# nixienet.net
KiCad netlist of a schematic drawn in EAGLE
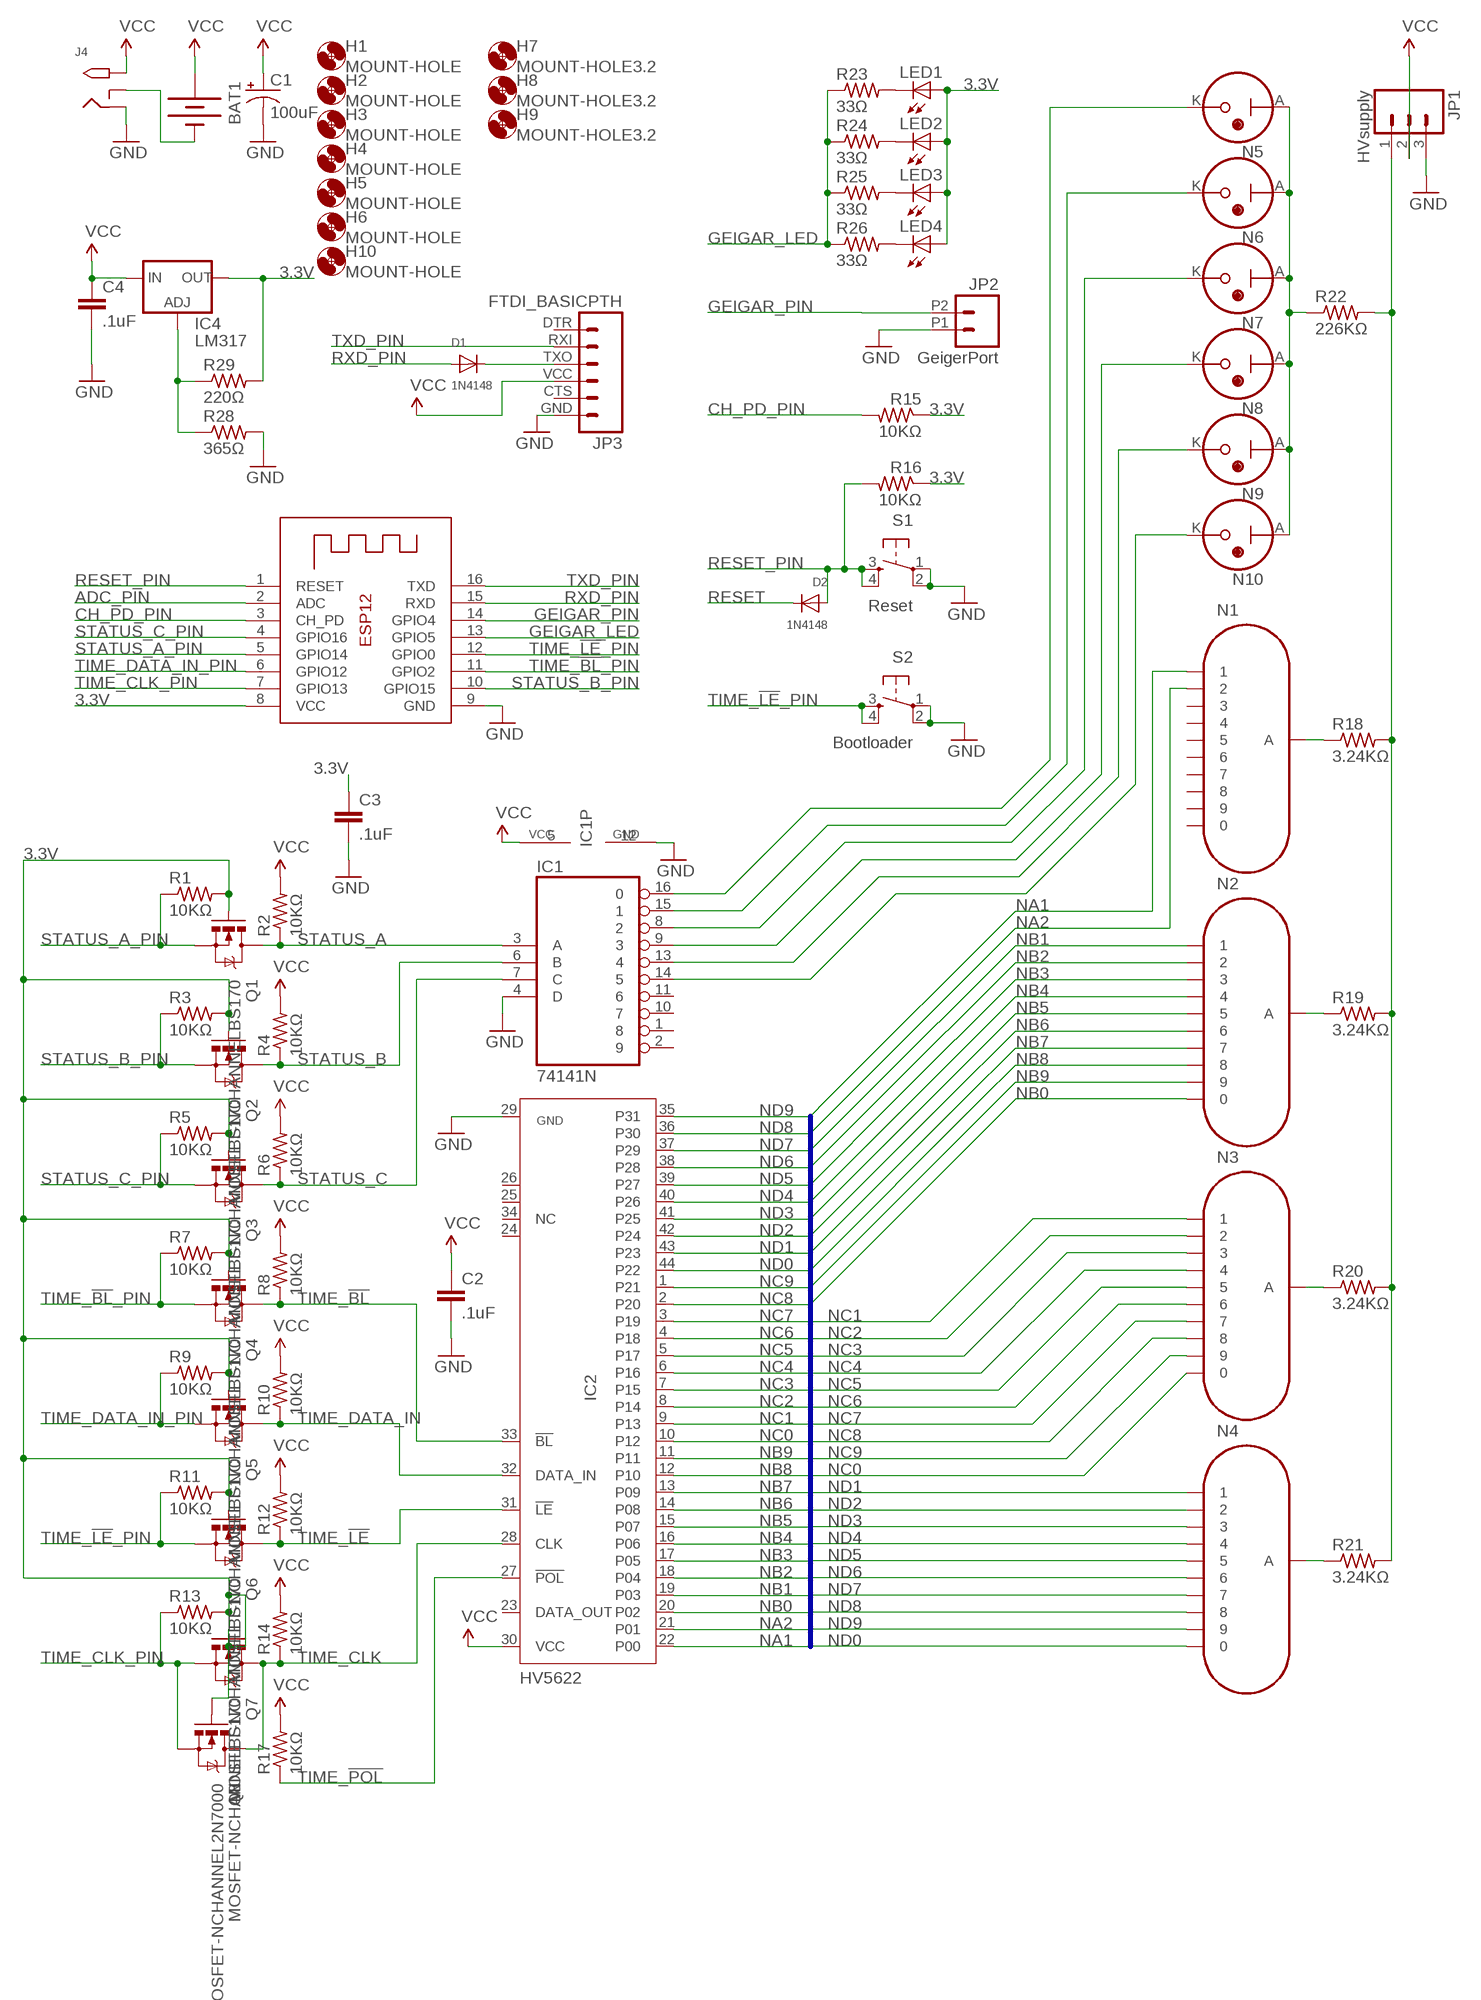
[diagram p0: schematic, sheet 1]

(export (version "E")
  (design (tool "Eeschema 10.0.6"))
  (components
    (comp (ref "BAT1")
      (value "BATTERY9V")
      (footprint "eagle-import:BATTCON_9V")
      (libsource (lib "eagle-import") (part "BATTERY9V"))
    )
    (comp (ref "C1")
      (value "100uF")
      (footprint "eagle-import:E5-8,5")
      (libsource (lib "eagle-import") (part "CPOL-USE5-8.5"))
    )
    (comp (ref "C2")
      (value ".1uF")
      (footprint "eagle-import:CAP-PTH-SMALLEZ")
      (libsource (lib "eagle-import") (part "CAPEZ"))
    )
    (comp (ref "C3")
      (value ".1uF")
      (footprint "eagle-import:CAP-PTH-SMALLEZ")
      (libsource (lib "eagle-import") (part "CAPEZ"))
    )
    (comp (ref "C4")
      (value ".1uF")
      (footprint "eagle-import:CAP-PTH-SMALLEZ")
      (libsource (lib "eagle-import") (part "CAPEZ"))
    )
    (comp (ref "D1")
      (value "1N4148")
      (footprint "eagle-import:1N4148")
      (libsource (lib "eagle-import") (part "DIODE"))
    )
    (comp (ref "D2")
      (value "1N4148")
      (footprint "eagle-import:1N4148")
      (libsource (lib "eagle-import") (part "DIODE"))
    )
    (comp (ref "H1")
      (value "MOUNT-HOLE")
      (footprint "eagle-import:3,2-DANGER")
      (libsource (lib "eagle-import") (part "MOUNT-HOLE"))
    )
    (comp (ref "H2")
      (value "MOUNT-HOLE")
      (footprint "eagle-import:3,2-DANGER")
      (libsource (lib "eagle-import") (part "MOUNT-HOLE"))
    )
    (comp (ref "H3")
      (value "MOUNT-HOLE")
      (footprint "eagle-import:3,2-DANGER")
      (libsource (lib "eagle-import") (part "MOUNT-HOLE"))
    )
    (comp (ref "H4")
      (value "MOUNT-HOLE")
      (footprint "eagle-import:3,2-DANGER")
      (libsource (lib "eagle-import") (part "MOUNT-HOLE"))
    )
    (comp (ref "H5")
      (value "MOUNT-HOLE")
      (footprint "eagle-import:3,2-DANGER")
      (libsource (lib "eagle-import") (part "MOUNT-HOLE"))
    )
    (comp (ref "H6")
      (value "MOUNT-HOLE")
      (footprint "eagle-import:3,2-DANGER")
      (libsource (lib "eagle-import") (part "MOUNT-HOLE"))
    )
    (comp (ref "H7")
      (value "MOUNT-HOLE3.2")
      (footprint "eagle-import:3,2")
      (libsource (lib "eagle-import") (part "MOUNT-HOLE3.2"))
    )
    (comp (ref "H8")
      (value "MOUNT-HOLE3.2")
      (footprint "eagle-import:3,2")
      (libsource (lib "eagle-import") (part "MOUNT-HOLE3.2"))
    )
    (comp (ref "H9")
      (value "MOUNT-HOLE3.2")
      (footprint "eagle-import:3,2")
      (libsource (lib "eagle-import") (part "MOUNT-HOLE3.2"))
    )
    (comp (ref "H10")
      (value "MOUNT-HOLE")
      (footprint "eagle-import:3,2-DANGER")
      (libsource (lib "eagle-import") (part "MOUNT-HOLE"))
    )
    (comp (ref "IC1")
      (value "74141N")
      (footprint "eagle-import:DIL16")
      (libsource (lib "eagle-import") (part "74141N"))
    )
    (comp (ref "IC2")
      (value "HV5622")
      (footprint "eagle-import:QFP44")
      (libsource (lib "eagle-import") (part "HV5622"))
    )
    (comp (ref "IC3")
      (value "ESP-12")
      (footprint "eagle-import:ESP-12")
      (libsource (lib "eagle-import") (part "ESP-12"))
    )
    (comp (ref "IC4")
      (value "LM317")
      (footprint "eagle-import:SPARKFUN-POWERIC_TO220-ADJ")
      (libsource (lib "eagle-import") (part "SPARKFUN-POWERIC_V_REG_317SINK"))
    )
    (comp (ref "J4")
      (value "2.1MMJACKTHM")
      (footprint "eagle-import:PJ-102A")
      (libsource (lib "eagle-import") (part "2.1MMJACKTHM"))
    )
    (comp (ref "JP1")
      (value "HVsupply")
      (footprint "eagle-import:SCREWTERMINAL-5MM-3")
      (libsource (lib "eagle-import") (part "M03-SCREW-5MM"))
    )
    (comp (ref "JP2")
      (value "GeigerPort")
      (footprint "eagle-import:1X02_2.54_SCREWTERM")
      (libsource (lib "eagle-import") (part "M022.54MM_SCREWTERM"))
    )
    (comp (ref "JP3")
      (value "FTDI_BASICPTH")
      (footprint "eagle-import:FTDI_BASIC")
      (libsource (lib "eagle-import") (part "FTDI_BASICPTH"))
    )
    (comp (ref "LED1")
      (value "LED5MM")
      (footprint "eagle-import:LED5MM")
      (libsource (lib "eagle-import") (part "LED5MM"))
    )
    (comp (ref "LED2")
      (value "LED5MM")
      (footprint "eagle-import:LED5MM")
      (libsource (lib "eagle-import") (part "LED5MM"))
    )
    (comp (ref "LED3")
      (value "LED5MM")
      (footprint "eagle-import:LED5MM")
      (libsource (lib "eagle-import") (part "LED5MM"))
    )
    (comp (ref "LED4")
      (value "LED5MM")
      (footprint "eagle-import:LED5MM")
      (libsource (lib "eagle-import") (part "LED5MM"))
    )
    (comp (ref "N1")
      (value "Hour1")
      (footprint "eagle-import:IN-18")
      (libsource (lib "eagle-import") (part "IN-4"))
    )
    (comp (ref "N2")
      (value "Hour2")
      (footprint "eagle-import:IN-18")
      (libsource (lib "eagle-import") (part "IN-4"))
    )
    (comp (ref "N3")
      (value "Minutes1")
      (footprint "eagle-import:IN-18")
      (libsource (lib "eagle-import") (part "IN-4"))
    )
    (comp (ref "N4")
      (value "Minutes2")
      (footprint "eagle-import:IN-18")
      (libsource (lib "eagle-import") (part "IN-4"))
    )
    (comp (ref "N5")
      (value "TopBulb")
      (footprint "eagle-import:INS-1")
      (libsource (lib "eagle-import") (part "INS-1"))
    )
    (comp (ref "N6")
      (value "BottomBulb")
      (footprint "eagle-import:INS-1")
      (libsource (lib "eagle-import") (part "INS-1"))
    )
    (comp (ref "N7")
      (value "SunnyBulb")
      (footprint "eagle-import:INS-1")
      (libsource (lib "eagle-import") (part "INS-1"))
    )
    (comp (ref "N8")
      (value "CloudyBulb")
      (footprint "eagle-import:INS-1")
      (libsource (lib "eagle-import") (part "INS-1"))
    )
    (comp (ref "N9")
      (value "RainyBulb")
      (footprint "eagle-import:INS-1")
      (libsource (lib "eagle-import") (part "INS-1"))
    )
    (comp (ref "N10")
      (value "SnowyBulb")
      (footprint "eagle-import:INS-1")
      (libsource (lib "eagle-import") (part "INS-1"))
    )
    (comp (ref "Q1")
      (value "MOSFET-NCHANNELBS170")
      (footprint "eagle-import:TO-92")
      (libsource (lib "eagle-import") (part "MOSFET-NCHANNELBS170"))
    )
    (comp (ref "Q2")
      (value "MOSFET-NCHANNELBS170")
      (footprint "eagle-import:TO-92")
      (libsource (lib "eagle-import") (part "MOSFET-NCHANNELBS170"))
    )
    (comp (ref "Q3")
      (value "MOSFET-NCHANNELBS170")
      (footprint "eagle-import:TO-92")
      (libsource (lib "eagle-import") (part "MOSFET-NCHANNELBS170"))
    )
    (comp (ref "Q4")
      (value "MOSFET-NCHANNELBS170")
      (footprint "eagle-import:TO-92")
      (libsource (lib "eagle-import") (part "MOSFET-NCHANNELBS170"))
    )
    (comp (ref "Q5")
      (value "MOSFET-NCHANNELBS170")
      (footprint "eagle-import:TO-92")
      (libsource (lib "eagle-import") (part "MOSFET-NCHANNELBS170"))
    )
    (comp (ref "Q6")
      (value "MOSFET-NCHANNELBS170")
      (footprint "eagle-import:TO-92")
      (libsource (lib "eagle-import") (part "MOSFET-NCHANNELBS170"))
    )
    (comp (ref "Q7")
      (value "MOSFET-NCHANNELBS170")
      (footprint "eagle-import:TO-92")
      (libsource (lib "eagle-import") (part "MOSFET-NCHANNELBS170"))
    )
    (comp (ref "Q8")
      (value "MOSFET-NCHANNEL2N7000")
      (footprint "eagle-import:TO-92")
      (libsource (lib "eagle-import") (part "MOSFET-NCHANNEL2N7000"))
    )
    (comp (ref "R1")
      (value "10KΩ")
      (footprint "eagle-import:0204_5")
      (libsource (lib "eagle-import") (part "R-US_0204/5"))
    )
    (comp (ref "R2")
      (value "10KΩ")
      (footprint "eagle-import:0204_5")
      (libsource (lib "eagle-import") (part "R-US_0204/5"))
    )
    (comp (ref "R3")
      (value "10KΩ")
      (footprint "eagle-import:0204_5")
      (libsource (lib "eagle-import") (part "R-US_0204/5"))
    )
    (comp (ref "R4")
      (value "10KΩ")
      (footprint "eagle-import:0204_5")
      (libsource (lib "eagle-import") (part "R-US_0204/5"))
    )
    (comp (ref "R5")
      (value "10KΩ")
      (footprint "eagle-import:0204_5")
      (libsource (lib "eagle-import") (part "R-US_0204/5"))
    )
    (comp (ref "R6")
      (value "10KΩ")
      (footprint "eagle-import:0204_5")
      (libsource (lib "eagle-import") (part "R-US_0204/5"))
    )
    (comp (ref "R7")
      (value "10KΩ")
      (footprint "eagle-import:0204_5")
      (libsource (lib "eagle-import") (part "R-US_0204/5"))
    )
    (comp (ref "R8")
      (value "10KΩ")
      (footprint "eagle-import:0204_5")
      (libsource (lib "eagle-import") (part "R-US_0204/5"))
    )
    (comp (ref "R9")
      (value "10KΩ")
      (footprint "eagle-import:0204_5")
      (libsource (lib "eagle-import") (part "R-US_0204/5"))
    )
    (comp (ref "R10")
      (value "10KΩ")
      (footprint "eagle-import:0204_5")
      (libsource (lib "eagle-import") (part "R-US_0204/5"))
    )
    (comp (ref "R11")
      (value "10KΩ")
      (footprint "eagle-import:0204_5")
      (libsource (lib "eagle-import") (part "R-US_0204/5"))
    )
    (comp (ref "R12")
      (value "10KΩ")
      (footprint "eagle-import:0204_5")
      (libsource (lib "eagle-import") (part "R-US_0204/5"))
    )
    (comp (ref "R13")
      (value "10KΩ")
      (footprint "eagle-import:0204_5")
      (libsource (lib "eagle-import") (part "R-US_0204/5"))
    )
    (comp (ref "R14")
      (value "10KΩ")
      (footprint "eagle-import:0204_5")
      (libsource (lib "eagle-import") (part "R-US_0204/5"))
    )
    (comp (ref "R15")
      (value "10KΩ")
      (footprint "eagle-import:0204_5")
      (libsource (lib "eagle-import") (part "R-US_0204/5"))
    )
    (comp (ref "R16")
      (value "10KΩ")
      (footprint "eagle-import:0204_5")
      (libsource (lib "eagle-import") (part "R-US_0204/5"))
    )
    (comp (ref "R17")
      (value "10KΩ")
      (footprint "eagle-import:0204_5")
      (libsource (lib "eagle-import") (part "R-US_0204/5"))
    )
    (comp (ref "R18")
      (value "3.24KΩ")
      (footprint "eagle-import:0204_5")
      (libsource (lib "eagle-import") (part "R-US_0204/5"))
    )
    (comp (ref "R19")
      (value "3.24KΩ")
      (footprint "eagle-import:0204_5")
      (libsource (lib "eagle-import") (part "R-US_0204/5"))
    )
    (comp (ref "R20")
      (value "3.24KΩ")
      (footprint "eagle-import:0204_5")
      (libsource (lib "eagle-import") (part "R-US_0204/5"))
    )
    (comp (ref "R21")
      (value "3.24KΩ")
      (footprint "eagle-import:0204_5")
      (libsource (lib "eagle-import") (part "R-US_0204/5"))
    )
    (comp (ref "R22")
      (value "226KΩ")
      (footprint "eagle-import:0204_5")
      (libsource (lib "eagle-import") (part "R-US_0204/5"))
    )
    (comp (ref "R23")
      (value "33Ω")
      (footprint "eagle-import:0204_5")
      (libsource (lib "eagle-import") (part "R-US_0204/5"))
    )
    (comp (ref "R24")
      (value "33Ω")
      (footprint "eagle-import:0204_5")
      (libsource (lib "eagle-import") (part "R-US_0204/5"))
    )
    (comp (ref "R25")
      (value "33Ω")
      (footprint "eagle-import:0204_5")
      (libsource (lib "eagle-import") (part "R-US_0204/5"))
    )
    (comp (ref "R26")
      (value "33Ω")
      (footprint "eagle-import:0204_5")
      (libsource (lib "eagle-import") (part "R-US_0204/5"))
    )
    (comp (ref "R28")
      (value "365Ω")
      (footprint "eagle-import:0204_5")
      (libsource (lib "eagle-import") (part "R-US_0204/5"))
    )
    (comp (ref "R29")
      (value "220Ω")
      (footprint "eagle-import:0204_5")
      (libsource (lib "eagle-import") (part "R-US_0204/5"))
    )
    (comp (ref "S1")
      (value "Reset")
      (footprint "eagle-import:TACTILE-PTH")
      (libsource (lib "eagle-import") (part "TAC_SWITCHPTH"))
    )
    (comp (ref "S2")
      (value "Bootloader")
      (footprint "eagle-import:TACTILE-PTH")
      (libsource (lib "eagle-import") (part "TAC_SWITCHPTH"))
    )
  )
  (nets
    (net (code "1") (name "/3.3V") (class "Default")
      (node (ref "C3") (pin "1") (pinfunction "1_1") (pintype "passive"))
      (node (ref "IC3") (pin "8") (pinfunction "VCC_8") (pintype "power_in"))
      (node (ref "IC4") (pin "OUT") (pinfunction "OUT_OUT") (pintype "output"))
      (node (ref "LED1") (pin "A") (pinfunction "A_A") (pintype "passive"))
      (node (ref "LED2") (pin "A") (pinfunction "A_A") (pintype "passive"))
      (node (ref "LED3") (pin "A") (pinfunction "A_A") (pintype "passive"))
      (node (ref "LED4") (pin "A") (pinfunction "A_A") (pintype "passive"))
      (node (ref "Q1") (pin "2") (pinfunction "G_2") (pintype "passive"))
      (node (ref "Q2") (pin "2") (pinfunction "G_2") (pintype "passive"))
      (node (ref "Q3") (pin "2") (pinfunction "G_2") (pintype "passive"))
      (node (ref "Q4") (pin "2") (pinfunction "G_2") (pintype "passive"))
      (node (ref "Q5") (pin "2") (pinfunction "G_2") (pintype "passive"))
      (node (ref "Q6") (pin "2") (pinfunction "G_2") (pintype "passive"))
      (node (ref "Q7") (pin "2") (pinfunction "G_2") (pintype "passive"))
      (node (ref "Q8") (pin "2") (pinfunction "G_2") (pintype "passive"))
      (node (ref "R1") (pin "2") (pinfunction "2_2") (pintype "passive"))
      (node (ref "R11") (pin "2") (pinfunction "2_2") (pintype "passive"))
      (node (ref "R13") (pin "2") (pinfunction "2_2") (pintype "passive"))
      (node (ref "R15") (pin "1") (pinfunction "1_1") (pintype "passive"))
      (node (ref "R16") (pin "1") (pinfunction "1_1") (pintype "passive"))
      (node (ref "R29") (pin "2") (pinfunction "2_2") (pintype "passive"))
      (node (ref "R3") (pin "2") (pinfunction "2_2") (pintype "passive"))
      (node (ref "R5") (pin "2") (pinfunction "2_2") (pintype "passive"))
      (node (ref "R7") (pin "2") (pinfunction "2_2") (pintype "passive"))
      (node (ref "R9") (pin "2") (pinfunction "2_2") (pintype "passive"))
    )
    (net (code "2") (name "/ADC_PIN") (class "Default")
      (node (ref "IC3") (pin "2") (pinfunction "ADC_2") (pintype "passive"))
    )
    (net (code "3") (name "/CH_PD_PIN") (class "Default")
      (node (ref "IC3") (pin "3") (pinfunction "CH_PD_3") (pintype "input"))
      (node (ref "R15") (pin "2") (pinfunction "2_2") (pintype "passive"))
    )
    (net (code "4") (name "/GEIGAR_LED") (class "Default")
      (node (ref "IC3") (pin "13") (pinfunction "GPIO5_13") (pintype "bidirectional"))
      (node (ref "R23") (pin "1") (pinfunction "1_1") (pintype "passive"))
      (node (ref "R24") (pin "1") (pinfunction "1_1") (pintype "passive"))
      (node (ref "R25") (pin "1") (pinfunction "1_1") (pintype "passive"))
      (node (ref "R26") (pin "1") (pinfunction "1_1") (pintype "passive"))
    )
    (net (code "5") (name "/GEIGAR_PIN") (class "Default")
      (node (ref "IC3") (pin "14") (pinfunction "GPIO4_14") (pintype "bidirectional"))
      (node (ref "JP2") (pin "P2") (pinfunction "2_P2") (pintype "passive"))
    )
    (net (code "6") (name "/NA1") (class "Default")
      (node (ref "IC2") (pin "22") (pinfunction "P00_22") (pintype "bidirectional"))
      (node (ref "N1") (pin "14") (pinfunction "1_14") (pintype "bidirectional"))
    )
    (net (code "7") (name "/NA2") (class "Default")
      (node (ref "IC2") (pin "21") (pinfunction "P01_21") (pintype "bidirectional"))
      (node (ref "N1") (pin "9") (pinfunction "2_9") (pintype "bidirectional"))
    )
    (net (code "8") (name "/NB0") (class "Default")
      (node (ref "IC2") (pin "20") (pinfunction "P02_20") (pintype "bidirectional"))
      (node (ref "N2") (pin "8") (pinfunction "0_8") (pintype "bidirectional"))
    )
    (net (code "9") (name "/NB1") (class "Default")
      (node (ref "IC2") (pin "19") (pinfunction "P03_19") (pintype "bidirectional"))
      (node (ref "N2") (pin "14") (pinfunction "1_14") (pintype "bidirectional"))
    )
    (net (code "10") (name "/NB2") (class "Default")
      (node (ref "IC2") (pin "18") (pinfunction "P04_18") (pintype "bidirectional"))
      (node (ref "N2") (pin "9") (pinfunction "2_9") (pintype "bidirectional"))
    )
    (net (code "11") (name "/NB3") (class "Default")
      (node (ref "IC2") (pin "17") (pinfunction "P05_17") (pintype "bidirectional"))
      (node (ref "N2") (pin "11") (pinfunction "3_11") (pintype "bidirectional"))
    )
    (net (code "12") (name "/NB4") (class "Default")
      (node (ref "IC2") (pin "16") (pinfunction "P06_16") (pintype "bidirectional"))
      (node (ref "N2") (pin "1") (pinfunction "4_1") (pintype "bidirectional"))
    )
    (net (code "13") (name "/NB5") (class "Default")
      (node (ref "IC2") (pin "15") (pinfunction "P07_15") (pintype "bidirectional"))
      (node (ref "N2") (pin "12") (pinfunction "5_12") (pintype "bidirectional"))
    )
    (net (code "14") (name "/NB6") (class "Default")
      (node (ref "IC2") (pin "14") (pinfunction "P08_14") (pintype "bidirectional"))
      (node (ref "N2") (pin "2") (pinfunction "6_2") (pintype "bidirectional"))
    )
    (net (code "15") (name "/NB7") (class "Default")
      (node (ref "IC2") (pin "13") (pinfunction "P09_13") (pintype "bidirectional"))
      (node (ref "N2") (pin "6") (pinfunction "7_6") (pintype "bidirectional"))
    )
    (net (code "16") (name "/NB8") (class "Default")
      (node (ref "IC2") (pin "12") (pinfunction "P10_12") (pintype "bidirectional"))
      (node (ref "N2") (pin "3") (pinfunction "8_3") (pintype "bidirectional"))
    )
    (net (code "17") (name "/NB9") (class "Default")
      (node (ref "IC2") (pin "11") (pinfunction "P11_11") (pintype "bidirectional"))
      (node (ref "N2") (pin "5") (pinfunction "9_5") (pintype "bidirectional"))
    )
    (net (code "18") (name "/NC0") (class "Default")
      (node (ref "IC2") (pin "10") (pinfunction "P12_10") (pintype "bidirectional"))
      (node (ref "N3") (pin "8") (pinfunction "0_8") (pintype "bidirectional"))
    )
    (net (code "19") (name "/NC1") (class "Default")
      (node (ref "IC2") (pin "9") (pinfunction "P13_9") (pintype "bidirectional"))
      (node (ref "N3") (pin "14") (pinfunction "1_14") (pintype "bidirectional"))
    )
    (net (code "20") (name "/NC2") (class "Default")
      (node (ref "IC2") (pin "8") (pinfunction "P14_8") (pintype "bidirectional"))
      (node (ref "N3") (pin "9") (pinfunction "2_9") (pintype "bidirectional"))
    )
    (net (code "21") (name "/NC3") (class "Default")
      (node (ref "IC2") (pin "7") (pinfunction "P15_7") (pintype "bidirectional"))
      (node (ref "N3") (pin "11") (pinfunction "3_11") (pintype "bidirectional"))
    )
    (net (code "22") (name "/NC4") (class "Default")
      (node (ref "IC2") (pin "6") (pinfunction "P16_6") (pintype "bidirectional"))
      (node (ref "N3") (pin "1") (pinfunction "4_1") (pintype "bidirectional"))
    )
    (net (code "23") (name "/NC5") (class "Default")
      (node (ref "IC2") (pin "5") (pinfunction "P17_5") (pintype "bidirectional"))
      (node (ref "N3") (pin "12") (pinfunction "5_12") (pintype "bidirectional"))
    )
    (net (code "24") (name "/NC6") (class "Default")
      (node (ref "IC2") (pin "4") (pinfunction "P18_4") (pintype "bidirectional"))
      (node (ref "N3") (pin "2") (pinfunction "6_2") (pintype "bidirectional"))
    )
    (net (code "25") (name "/NC7") (class "Default")
      (node (ref "IC2") (pin "3") (pinfunction "P19_3") (pintype "bidirectional"))
      (node (ref "N3") (pin "6") (pinfunction "7_6") (pintype "bidirectional"))
    )
    (net (code "26") (name "/NC8") (class "Default")
      (node (ref "IC2") (pin "2") (pinfunction "P20_2") (pintype "bidirectional"))
      (node (ref "N3") (pin "3") (pinfunction "8_3") (pintype "bidirectional"))
    )
    (net (code "27") (name "/NC9") (class "Default")
      (node (ref "IC2") (pin "1") (pinfunction "P21_1") (pintype "bidirectional"))
      (node (ref "N3") (pin "5") (pinfunction "9_5") (pintype "bidirectional"))
    )
    (net (code "28") (name "/ND0") (class "Default")
      (node (ref "IC2") (pin "44") (pinfunction "P22_44") (pintype "bidirectional"))
      (node (ref "N4") (pin "8") (pinfunction "0_8") (pintype "bidirectional"))
    )
    (net (code "29") (name "/ND1") (class "Default")
      (node (ref "IC2") (pin "43") (pinfunction "P23_43") (pintype "bidirectional"))
      (node (ref "N4") (pin "14") (pinfunction "1_14") (pintype "bidirectional"))
    )
    (net (code "30") (name "/ND2") (class "Default")
      (node (ref "IC2") (pin "42") (pinfunction "P24_42") (pintype "bidirectional"))
      (node (ref "N4") (pin "9") (pinfunction "2_9") (pintype "bidirectional"))
    )
    (net (code "31") (name "/ND3") (class "Default")
      (node (ref "IC2") (pin "41") (pinfunction "P25_41") (pintype "bidirectional"))
      (node (ref "N4") (pin "11") (pinfunction "3_11") (pintype "bidirectional"))
    )
    (net (code "32") (name "/ND4") (class "Default")
      (node (ref "IC2") (pin "40") (pinfunction "P26_40") (pintype "bidirectional"))
      (node (ref "N4") (pin "1") (pinfunction "4_1") (pintype "bidirectional"))
    )
    (net (code "33") (name "/ND5") (class "Default")
      (node (ref "IC2") (pin "39") (pinfunction "P27_39") (pintype "bidirectional"))
      (node (ref "N4") (pin "12") (pinfunction "5_12") (pintype "bidirectional"))
    )
    (net (code "34") (name "/ND6") (class "Default")
      (node (ref "IC2") (pin "38") (pinfunction "P28_38") (pintype "bidirectional"))
      (node (ref "N4") (pin "2") (pinfunction "6_2") (pintype "bidirectional"))
    )
    (net (code "35") (name "/ND7") (class "Default")
      (node (ref "IC2") (pin "37") (pinfunction "P29_37") (pintype "bidirectional"))
      (node (ref "N4") (pin "6") (pinfunction "7_6") (pintype "bidirectional"))
    )
    (net (code "36") (name "/ND8") (class "Default")
      (node (ref "IC2") (pin "36") (pinfunction "P30_36") (pintype "bidirectional"))
      (node (ref "N4") (pin "3") (pinfunction "8_3") (pintype "bidirectional"))
    )
    (net (code "37") (name "/ND9") (class "Default")
      (node (ref "IC2") (pin "35") (pinfunction "P31_35") (pintype "bidirectional"))
      (node (ref "N4") (pin "5") (pinfunction "9_5") (pintype "bidirectional"))
    )
    (net (code "38") (name "/RESET") (class "Default")
      (node (ref "D2") (pin "K") (pinfunction "C_K") (pintype "passive"))
    )
    (net (code "39") (name "/RESET_PIN") (class "Default")
      (node (ref "D2") (pin "A") (pinfunction "A_A") (pintype "passive"))
      (node (ref "IC3") (pin "1") (pinfunction "RESET_1") (pintype "input"))
      (node (ref "R16") (pin "2") (pinfunction "2_2") (pintype "passive"))
      (node (ref "S1") (pin "3") (pinfunction "3_3") (pintype "passive"))
      (node (ref "S1") (pin "4") (pinfunction "4_4") (pintype "passive"))
    )
    (net (code "40") (name "/RXD_PIN") (class "Default")
      (node (ref "D1") (pin "A") (pinfunction "A_A") (pintype "passive"))
      (node (ref "IC3") (pin "15") (pinfunction "RXD_15") (pintype "input"))
    )
    (net (code "41") (name "/STATUS_A") (class "Default")
      (node (ref "IC1") (pin "3") (pinfunction "A_3") (pintype "input"))
      (node (ref "Q1") (pin "1") (pinfunction "D_1") (pintype "passive"))
      (node (ref "R2") (pin "1") (pinfunction "1_1") (pintype "passive"))
    )
    (net (code "42") (name "/STATUS_A_PIN") (class "Default")
      (node (ref "IC3") (pin "5") (pinfunction "GPIO14_5") (pintype "bidirectional"))
      (node (ref "Q1") (pin "3") (pinfunction "S_3") (pintype "passive"))
      (node (ref "R1") (pin "1") (pinfunction "1_1") (pintype "passive"))
    )
    (net (code "43") (name "/STATUS_B") (class "Default")
      (node (ref "IC1") (pin "6") (pinfunction "B_6") (pintype "input"))
      (node (ref "Q2") (pin "1") (pinfunction "D_1") (pintype "passive"))
      (node (ref "R4") (pin "1") (pinfunction "1_1") (pintype "passive"))
    )
    (net (code "44") (name "/STATUS_B_PIN") (class "Default")
      (node (ref "IC3") (pin "10") (pinfunction "GPIO15_10") (pintype "bidirectional"))
      (node (ref "Q2") (pin "3") (pinfunction "S_3") (pintype "passive"))
      (node (ref "R3") (pin "1") (pinfunction "1_1") (pintype "passive"))
    )
    (net (code "45") (name "/STATUS_C") (class "Default")
      (node (ref "IC1") (pin "7") (pinfunction "C_7") (pintype "input"))
      (node (ref "Q3") (pin "1") (pinfunction "D_1") (pintype "passive"))
      (node (ref "R6") (pin "1") (pinfunction "1_1") (pintype "passive"))
    )
    (net (code "46") (name "/STATUS_C_PIN") (class "Default")
      (node (ref "IC3") (pin "4") (pinfunction "GPIO16_4") (pintype "bidirectional"))
      (node (ref "Q3") (pin "3") (pinfunction "S_3") (pintype "passive"))
      (node (ref "R5") (pin "1") (pinfunction "1_1") (pintype "passive"))
    )
    (net (code "47") (name "/TIME_CLK") (class "Default")
      (node (ref "IC2") (pin "28") (pinfunction "CLK_28") (pintype "input"))
      (node (ref "Q7") (pin "1") (pinfunction "D_1") (pintype "passive"))
      (node (ref "Q8") (pin "3") (pinfunction "D_3") (pintype "passive"))
      (node (ref "R14") (pin "1") (pinfunction "1_1") (pintype "passive"))
    )
    (net (code "48") (name "/TIME_CLK_PIN") (class "Default")
      (node (ref "IC3") (pin "7") (pinfunction "GPIO13_7") (pintype "bidirectional"))
      (node (ref "Q7") (pin "3") (pinfunction "S_3") (pintype "passive"))
      (node (ref "Q8") (pin "1") (pinfunction "S_1") (pintype "passive"))
      (node (ref "R13") (pin "1") (pinfunction "1_1") (pintype "passive"))
    )
    (net (code "49") (name "/TIME_DATA_IN") (class "Default")
      (node (ref "IC2") (pin "32") (pinfunction "DATA_IN_32") (pintype "input"))
      (node (ref "Q5") (pin "1") (pinfunction "D_1") (pintype "passive"))
      (node (ref "R10") (pin "1") (pinfunction "1_1") (pintype "passive"))
    )
    (net (code "50") (name "/TIME_DATA_IN_PIN") (class "Default")
      (node (ref "IC3") (pin "6") (pinfunction "GPIO12_6") (pintype "bidirectional"))
      (node (ref "Q5") (pin "3") (pinfunction "S_3") (pintype "passive"))
      (node (ref "R9") (pin "1") (pinfunction "1_1") (pintype "passive"))
    )
    (net (code "51") (name "/TIME_~{BL}") (class "Default")
      (node (ref "IC2") (pin "33") (pinfunction "~{BL}_33") (pintype "input"))
      (node (ref "Q4") (pin "1") (pinfunction "D_1") (pintype "passive"))
      (node (ref "R8") (pin "1") (pinfunction "1_1") (pintype "passive"))
    )
    (net (code "52") (name "/TIME_~{BL}_PIN") (class "Default")
      (node (ref "IC3") (pin "11") (pinfunction "GPIO2_11") (pintype "bidirectional"))
      (node (ref "Q4") (pin "3") (pinfunction "S_3") (pintype "passive"))
      (node (ref "R7") (pin "1") (pinfunction "1_1") (pintype "passive"))
    )
    (net (code "53") (name "/TIME_~{LE}") (class "Default")
      (node (ref "IC2") (pin "31") (pinfunction "~{LE}_31") (pintype "input"))
      (node (ref "Q6") (pin "1") (pinfunction "D_1") (pintype "passive"))
      (node (ref "R12") (pin "1") (pinfunction "1_1") (pintype "passive"))
    )
    (net (code "54") (name "/TIME_~{LE}_PIN") (class "Default")
      (node (ref "IC3") (pin "12") (pinfunction "GPIO0_12") (pintype "bidirectional"))
      (node (ref "Q6") (pin "3") (pinfunction "S_3") (pintype "passive"))
      (node (ref "R11") (pin "1") (pinfunction "1_1") (pintype "passive"))
      (node (ref "S2") (pin "3") (pinfunction "3_3") (pintype "passive"))
      (node (ref "S2") (pin "4") (pinfunction "4_4") (pintype "passive"))
    )
    (net (code "55") (name "/TIME_~{POL}") (class "Default")
      (node (ref "IC2") (pin "27") (pinfunction "~{POL}_27") (pintype "input"))
      (node (ref "R17") (pin "1") (pinfunction "1_1") (pintype "passive"))
    )
    (net (code "56") (name "/TXD_PIN") (class "Default")
      (node (ref "IC3") (pin "16") (pinfunction "TXD_16") (pintype "output"))
      (node (ref "JP3") (pin "RXI") (pinfunction "2_RXI") (pintype "passive"))
    )
    (net (code "57") (name "GND") (class "Default")
      (node (ref "C1") (pin "-") (pinfunction "-_-") (pintype "passive"))
      (node (ref "C2") (pin "2") (pinfunction "2_2") (pintype "passive"))
      (node (ref "C3") (pin "2") (pinfunction "2_2") (pintype "passive"))
      (node (ref "C4") (pin "2") (pinfunction "2_2") (pintype "passive"))
      (node (ref "IC1") (pin "12") (pinfunction "GND_12") (pintype "power_in"))
      (node (ref "IC1") (pin "4") (pinfunction "D_4") (pintype "input"))
      (node (ref "IC2") (pin "29") (pinfunction "GND_29") (pintype "power_in"))
      (node (ref "IC3") (pin "9") (pinfunction "GND_9") (pintype "power_in"))
      (node (ref "J4") (pin "RING") (pinfunction "RING_RING") (pintype "bidirectional"))
      (node (ref "JP1") (pin "3") (pinfunction "3_3") (pintype "passive"))
      (node (ref "JP2") (pin "P1") (pinfunction "1_P1") (pintype "passive"))
      (node (ref "JP3") (pin "GND") (pinfunction "6_GND") (pintype "passive"))
      (node (ref "R28") (pin "2") (pinfunction "2_2") (pintype "passive"))
      (node (ref "S1") (pin "1") (pinfunction "1_1") (pintype "passive"))
      (node (ref "S1") (pin "2") (pinfunction "2_2") (pintype "passive"))
      (node (ref "S2") (pin "1") (pinfunction "1_1") (pintype "passive"))
      (node (ref "S2") (pin "2") (pinfunction "2_2") (pintype "passive"))
    )
    (net (code "58") (name "Net-(BAT1-Pad-)") (class "Default")
      (node (ref "BAT1") (pin "-") (pinfunction "-_-") (pintype "power_in"))
      (node (ref "J4") (pin "RING_SW") (pinfunction "RING_SW_RING_SW") (pintype "bidirectional"))
    )
    (net (code "59") (name "Net-(D1-C)") (class "Default")
      (node (ref "D1") (pin "K") (pinfunction "C_K") (pintype "passive"))
      (node (ref "JP3") (pin "TXO") (pinfunction "3_TXO") (pintype "passive"))
    )
    (net (code "60") (name "Net-(IC1A-0)") (class "Default")
      (node (ref "IC1") (pin "16") (pinfunction "0_16") (pintype "open_collector"))
      (node (ref "N5") (pin "K") (pinfunction "K_K") (pintype "bidirectional"))
    )
    (net (code "61") (name "Net-(IC1A-1)") (class "Default")
      (node (ref "IC1") (pin "15") (pinfunction "1_15") (pintype "open_collector"))
      (node (ref "N6") (pin "K") (pinfunction "K_K") (pintype "bidirectional"))
    )
    (net (code "62") (name "Net-(IC1A-2)") (class "Default")
      (node (ref "IC1") (pin "8") (pinfunction "2_8") (pintype "open_collector"))
      (node (ref "N7") (pin "K") (pinfunction "K_K") (pintype "bidirectional"))
    )
    (net (code "63") (name "Net-(IC1A-3)") (class "Default")
      (node (ref "IC1") (pin "9") (pinfunction "3_9") (pintype "open_collector"))
      (node (ref "N8") (pin "K") (pinfunction "K_K") (pintype "bidirectional"))
    )
    (net (code "64") (name "Net-(IC1A-4)") (class "Default")
      (node (ref "IC1") (pin "13") (pinfunction "4_13") (pintype "open_collector"))
      (node (ref "N9") (pin "K") (pinfunction "K_K") (pintype "bidirectional"))
    )
    (net (code "65") (name "Net-(IC1A-5)") (class "Default")
      (node (ref "IC1") (pin "14") (pinfunction "5_14") (pintype "open_collector"))
      (node (ref "N10") (pin "K") (pinfunction "K_K") (pintype "bidirectional"))
    )
    (net (code "66") (name "Net-(IC4-PadADJ)") (class "Default")
      (node (ref "IC4") (pin "ADJ") (pinfunction "ADJ_ADJ") (pintype "input"))
      (node (ref "R28") (pin "1") (pinfunction "1_1") (pintype "passive"))
      (node (ref "R29") (pin "1") (pinfunction "1_1") (pintype "passive"))
    )
    (net (code "67") (name "Net-(JP1-Pad1)") (class "Default")
      (node (ref "JP1") (pin "1") (pinfunction "1_1") (pintype "passive"))
      (node (ref "R18") (pin "2") (pinfunction "2_2") (pintype "passive"))
      (node (ref "R19") (pin "2") (pinfunction "2_2") (pintype "passive"))
      (node (ref "R20") (pin "2") (pinfunction "2_2") (pintype "passive"))
      (node (ref "R21") (pin "2") (pinfunction "2_2") (pintype "passive"))
      (node (ref "R22") (pin "2") (pinfunction "2_2") (pintype "passive"))
    )
    (net (code "68") (name "Net-(LED1-C)") (class "Default")
      (node (ref "LED1") (pin "K") (pinfunction "C_K") (pintype "passive"))
      (node (ref "R23") (pin "2") (pinfunction "2_2") (pintype "passive"))
    )
    (net (code "69") (name "Net-(LED2-C)") (class "Default")
      (node (ref "LED2") (pin "K") (pinfunction "C_K") (pintype "passive"))
      (node (ref "R24") (pin "2") (pinfunction "2_2") (pintype "passive"))
    )
    (net (code "70") (name "Net-(LED3-C)") (class "Default")
      (node (ref "LED3") (pin "K") (pinfunction "C_K") (pintype "passive"))
      (node (ref "R25") (pin "2") (pinfunction "2_2") (pintype "passive"))
    )
    (net (code "71") (name "Net-(LED4-C)") (class "Default")
      (node (ref "LED4") (pin "K") (pinfunction "C_K") (pintype "passive"))
      (node (ref "R26") (pin "2") (pinfunction "2_2") (pintype "passive"))
    )
    (net (code "72") (name "Net-(N1-A)") (class "Default")
      (node (ref "N1") (pin "4") (pinfunction "A_4") (pintype "bidirectional"))
      (node (ref "R18") (pin "1") (pinfunction "1_1") (pintype "passive"))
    )
    (net (code "73") (name "Net-(N2-A)") (class "Default")
      (node (ref "N2") (pin "4") (pinfunction "A_4") (pintype "bidirectional"))
      (node (ref "R19") (pin "1") (pinfunction "1_1") (pintype "passive"))
    )
    (net (code "74") (name "Net-(N3-A)") (class "Default")
      (node (ref "N3") (pin "4") (pinfunction "A_4") (pintype "bidirectional"))
      (node (ref "R20") (pin "1") (pinfunction "1_1") (pintype "passive"))
    )
    (net (code "75") (name "Net-(N4-A)") (class "Default")
      (node (ref "N4") (pin "4") (pinfunction "A_4") (pintype "bidirectional"))
      (node (ref "R21") (pin "1") (pinfunction "1_1") (pintype "passive"))
    )
    (net (code "76") (name "Net-(N10-PadA)") (class "Default")
      (node (ref "N10") (pin "A") (pinfunction "A_A") (pintype "bidirectional"))
      (node (ref "N5") (pin "A") (pinfunction "A_A") (pintype "bidirectional"))
      (node (ref "N6") (pin "A") (pinfunction "A_A") (pintype "bidirectional"))
      (node (ref "N7") (pin "A") (pinfunction "A_A") (pintype "bidirectional"))
      (node (ref "N8") (pin "A") (pinfunction "A_A") (pintype "bidirectional"))
      (node (ref "N9") (pin "A") (pinfunction "A_A") (pintype "bidirectional"))
      (node (ref "R22") (pin "1") (pinfunction "1_1") (pintype "passive"))
    )
    (net (code "77") (name "VCC") (class "Default")
      (node (ref "BAT1") (pin "+") (pinfunction "+_+") (pintype "power_in"))
      (node (ref "C1") (pin "+") (pinfunction "+_+") (pintype "passive"))
      (node (ref "C2") (pin "1") (pinfunction "1_1") (pintype "passive"))
      (node (ref "C4") (pin "1") (pinfunction "1_1") (pintype "passive"))
      (node (ref "IC1") (pin "5") (pinfunction "VCC_5") (pintype "power_in"))
      (node (ref "IC2") (pin "30") (pinfunction "VCC_30") (pintype "power_in"))
      (node (ref "IC4") (pin "IN") (pinfunction "IN_IN") (pintype "input"))
      (node (ref "J4") (pin "TIP") (pinfunction "TIP_TIP") (pintype "bidirectional"))
      (node (ref "JP1") (pin "2") (pinfunction "2_2") (pintype "passive"))
      (node (ref "JP3") (pin "VCC") (pinfunction "4_VCC") (pintype "passive"))
      (node (ref "R10") (pin "2") (pinfunction "2_2") (pintype "passive"))
      (node (ref "R12") (pin "2") (pinfunction "2_2") (pintype "passive"))
      (node (ref "R14") (pin "2") (pinfunction "2_2") (pintype "passive"))
      (node (ref "R17") (pin "2") (pinfunction "2_2") (pintype "passive"))
      (node (ref "R2") (pin "2") (pinfunction "2_2") (pintype "passive"))
      (node (ref "R4") (pin "2") (pinfunction "2_2") (pintype "passive"))
      (node (ref "R6") (pin "2") (pinfunction "2_2") (pintype "passive"))
      (node (ref "R8") (pin "2") (pinfunction "2_2") (pintype "passive"))
    )
    (net (code "78") (name "unconnected-(IC1A-6-Pad11)") (class "Default")
      (node (ref "IC1") (pin "11") (pinfunction "6_11") (pintype "open_collector"))
    )
    (net (code "79") (name "unconnected-(IC1A-7-Pad10)") (class "Default")
      (node (ref "IC1") (pin "10") (pinfunction "7_10") (pintype "open_collector"))
    )
    (net (code "80") (name "unconnected-(IC1A-8-Pad1)") (class "Default")
      (node (ref "IC1") (pin "1") (pinfunction "8_1") (pintype "open_collector"))
    )
    (net (code "81") (name "unconnected-(IC1A-9-Pad2)") (class "Default")
      (node (ref "IC1") (pin "2") (pinfunction "9_2") (pintype "open_collector"))
    )
    (net (code "82") (name "unconnected-(IC2-DATA_OUT-Pad23)") (class "Default")
      (node (ref "IC2") (pin "23") (pinfunction "DATA_OUT_23") (pintype "output"))
    )
    (net (code "83") (name "unconnected-(IC2-NC-Pad24)") (class "Default")
      (node (ref "IC2") (pin "24") (pinfunction "NC_24") (pintype "bidirectional"))
    )
    (net (code "84") (name "unconnected-(IC2-NC-Pad25)") (class "Default")
      (node (ref "IC2") (pin "25") (pinfunction "NC_25") (pintype "bidirectional"))
    )
    (net (code "85") (name "unconnected-(IC2-NC-Pad26)") (class "Default")
      (node (ref "IC2") (pin "26") (pinfunction "NC_26") (pintype "bidirectional"))
    )
    (net (code "86") (name "unconnected-(IC2-NC-Pad34)") (class "Default")
      (node (ref "IC2") (pin "34") (pinfunction "NC_34") (pintype "bidirectional"))
    )
    (net (code "87") (name "unconnected-(JP3-1-PadDTR)") (class "Default")
      (node (ref "JP3") (pin "DTR") (pinfunction "1_DTR") (pintype "passive"))
    )
    (net (code "88") (name "unconnected-(JP3-5-PadCTS)") (class "Default")
      (node (ref "JP3") (pin "CTS") (pinfunction "5_CTS") (pintype "passive"))
    )
    (net (code "89") (name "unconnected-(N1-0-Pad8)") (class "Default")
      (node (ref "N1") (pin "8") (pinfunction "0_8") (pintype "bidirectional"))
    )
    (net (code "90") (name "unconnected-(N1-3-Pad11)") (class "Default")
      (node (ref "N1") (pin "11") (pinfunction "3_11") (pintype "bidirectional"))
    )
    (net (code "91") (name "unconnected-(N1-4-Pad1)") (class "Default")
      (node (ref "N1") (pin "1") (pinfunction "4_1") (pintype "bidirectional"))
    )
    (net (code "92") (name "unconnected-(N1-5-Pad12)") (class "Default")
      (node (ref "N1") (pin "12") (pinfunction "5_12") (pintype "bidirectional"))
    )
    (net (code "93") (name "unconnected-(N1-6-Pad2)") (class "Default")
      (node (ref "N1") (pin "2") (pinfunction "6_2") (pintype "bidirectional"))
    )
    (net (code "94") (name "unconnected-(N1-7-Pad6)") (class "Default")
      (node (ref "N1") (pin "6") (pinfunction "7_6") (pintype "bidirectional"))
    )
    (net (code "95") (name "unconnected-(N1-8-Pad3)") (class "Default")
      (node (ref "N1") (pin "3") (pinfunction "8_3") (pintype "bidirectional"))
    )
    (net (code "96") (name "unconnected-(N1-9-Pad5)") (class "Default")
      (node (ref "N1") (pin "5") (pinfunction "9_5") (pintype "bidirectional"))
    )
  )
)
